# open-lab-VUSB-D.net
KiCad netlist of a schematic drawn in EAGLE
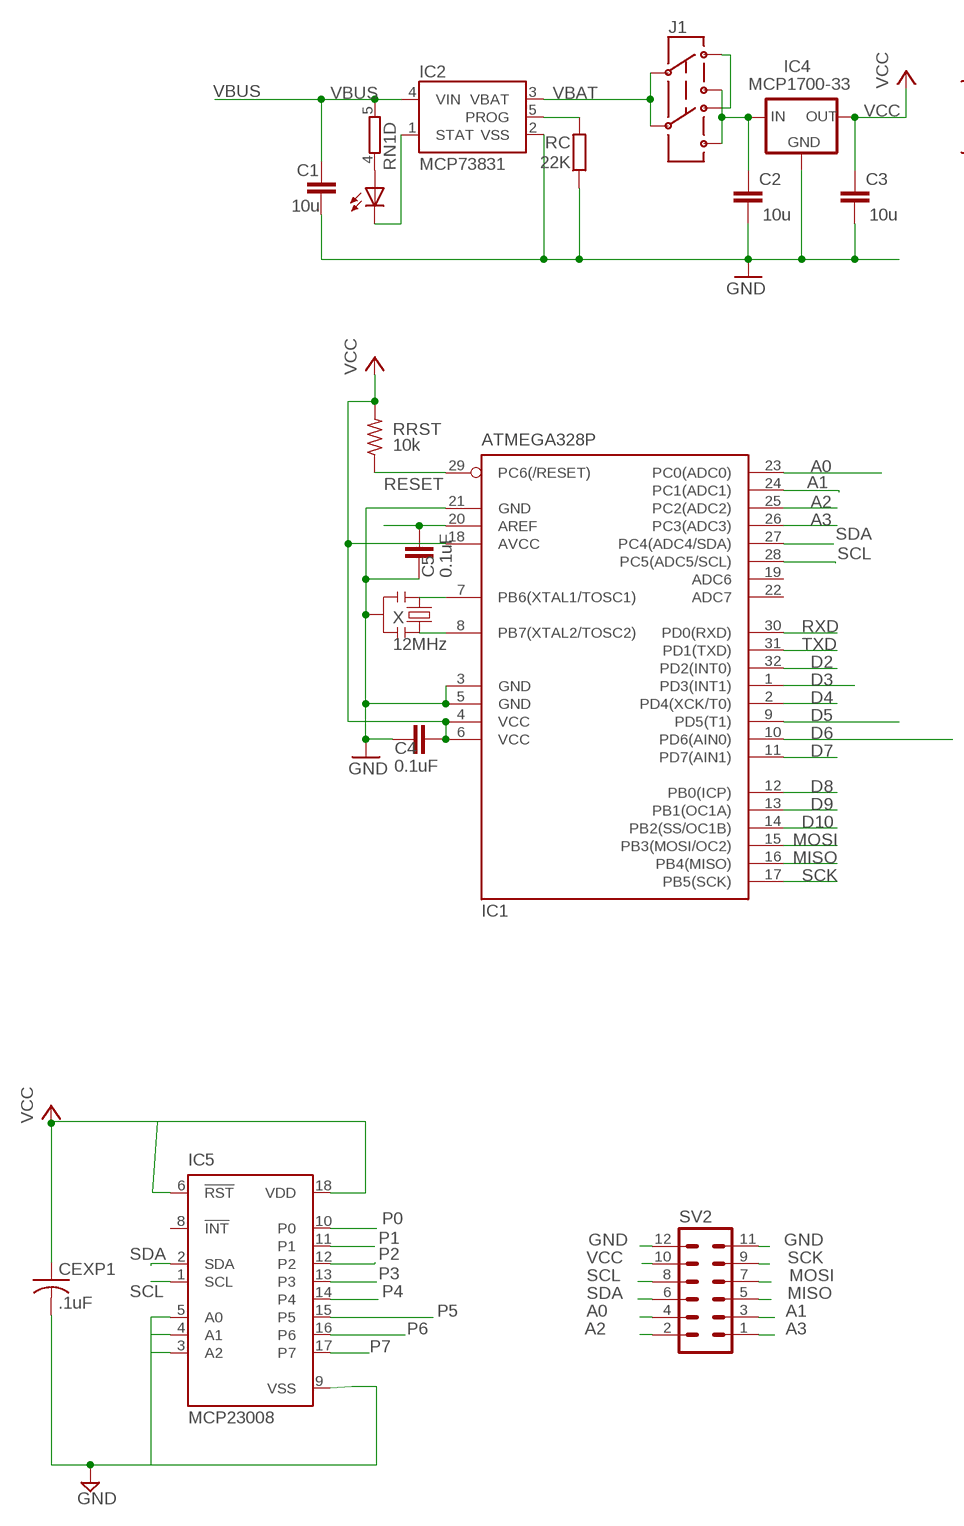
[diagram p0: schematic, sheet 1, part 1 of 2]
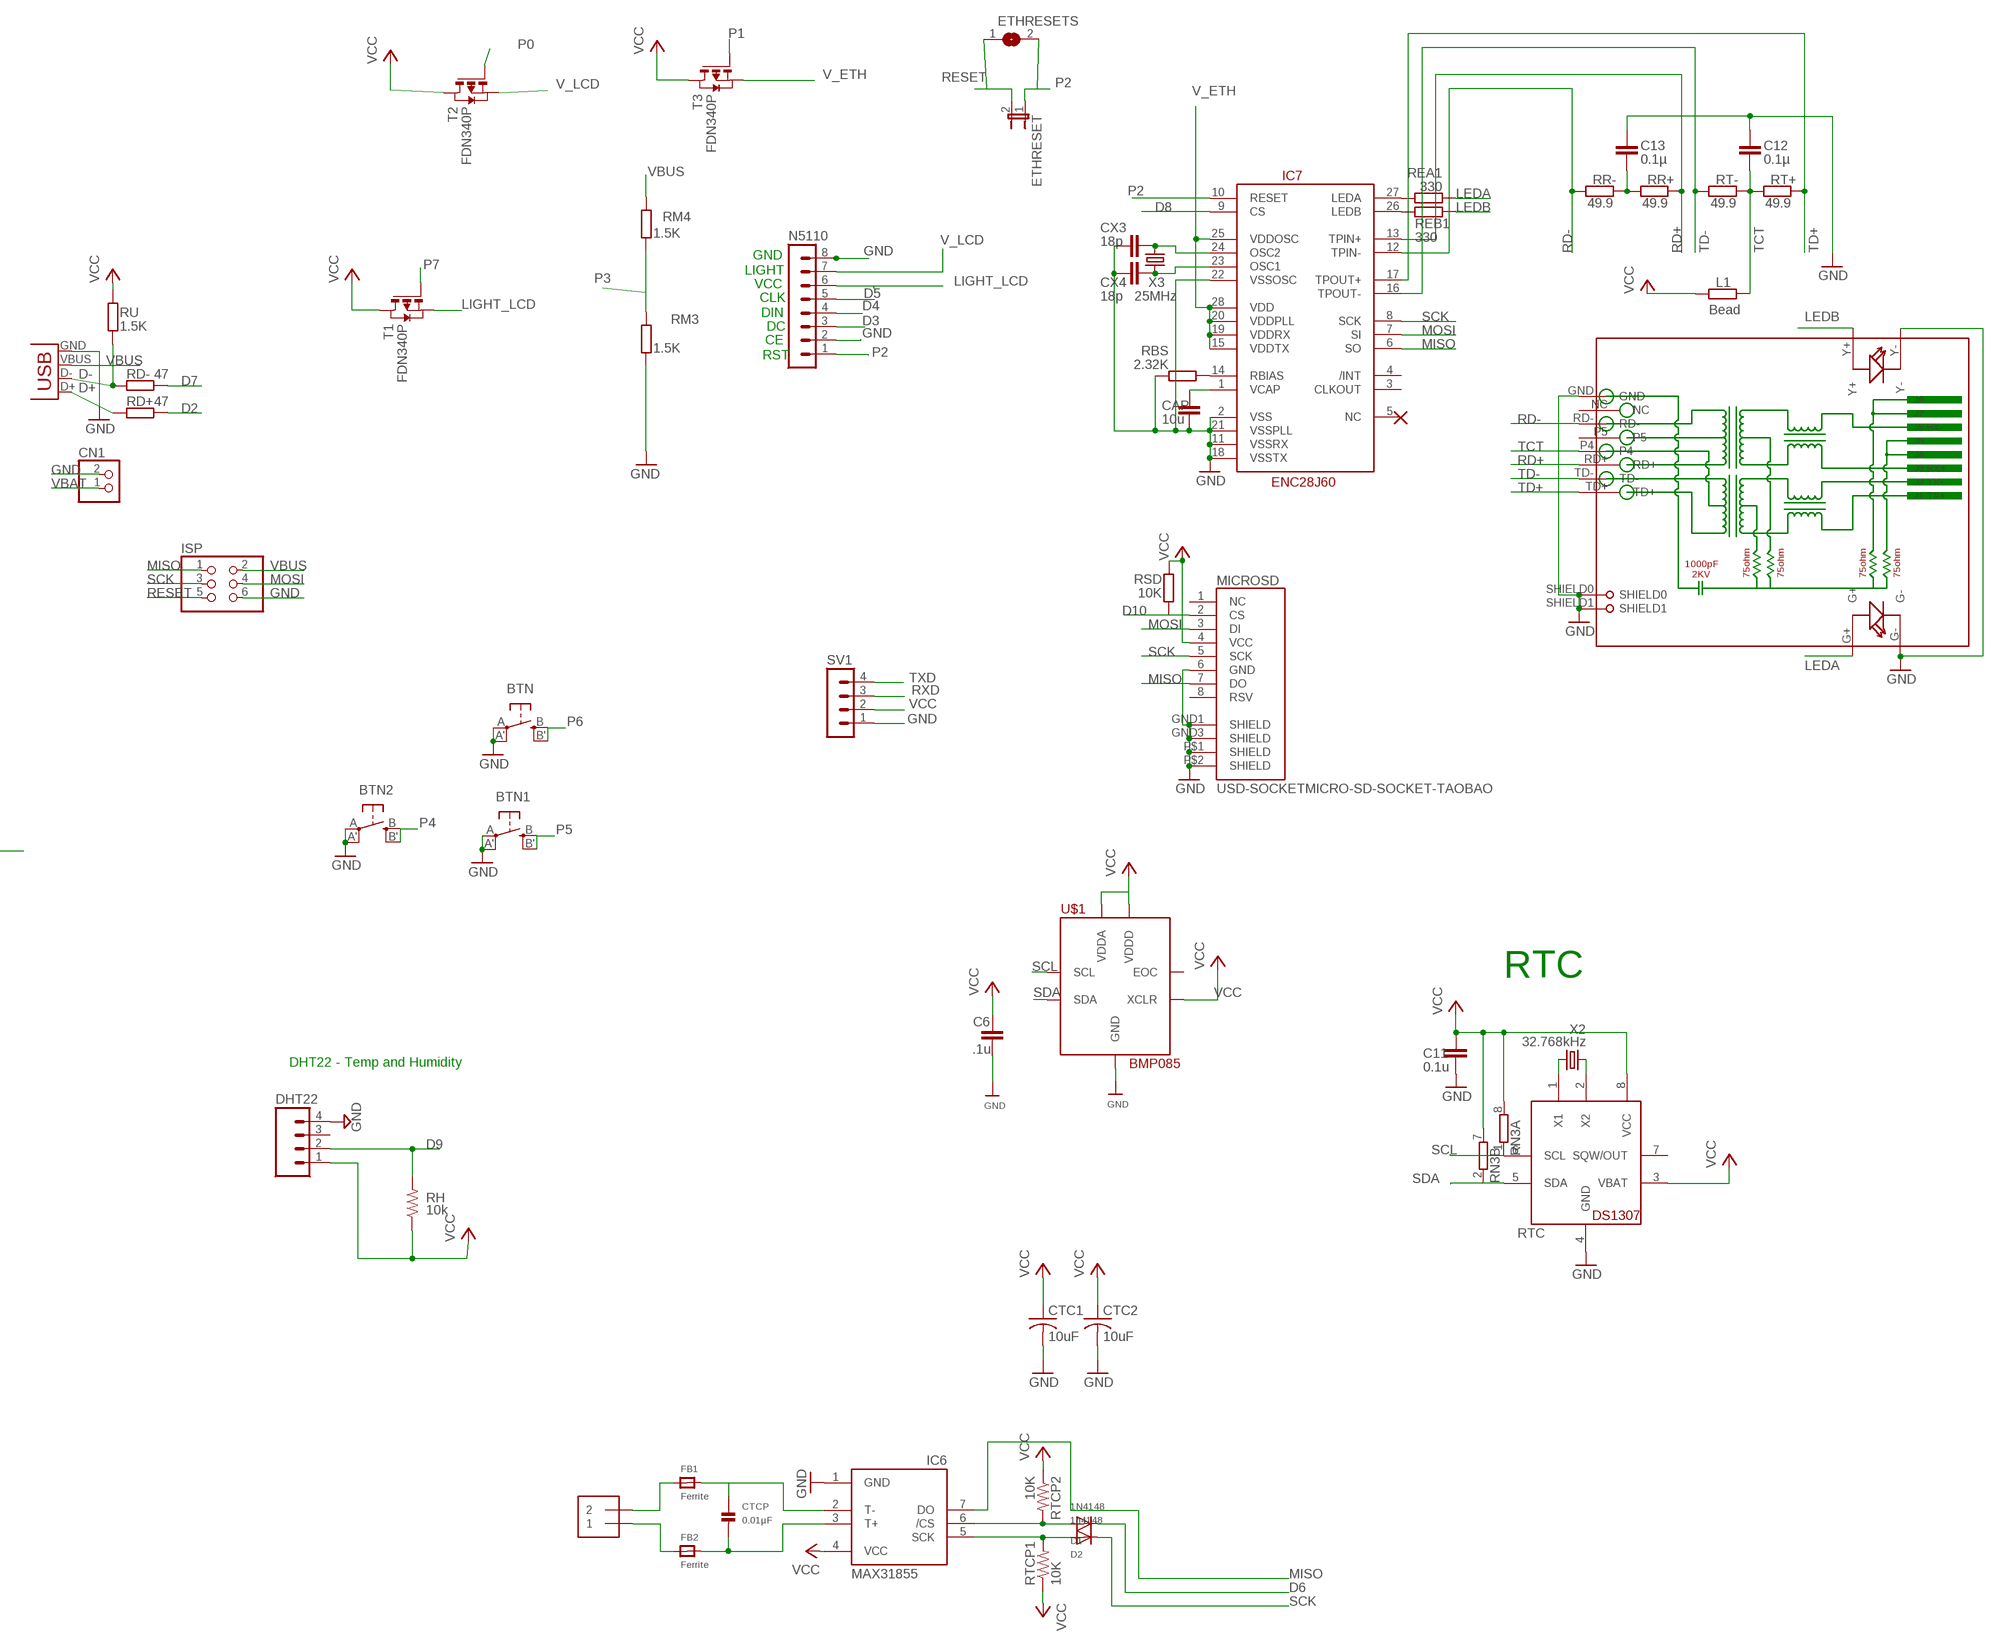
[diagram p1: schematic, sheet 1, part 2 of 2]

(export (version "E")
  (design (tool "Eeschema 10.0.6"))
  (components
    (comp (ref "BTN")
      (value "EVQQ2")
      (footprint "eagle-import:EVQ-Q2")
      (libsource (lib "eagle-import") (part "EVQQ2"))
    )
    (comp (ref "BTN1")
      (value "EVQQ2")
      (footprint "eagle-import:EVQ-Q2")
      (libsource (lib "eagle-import") (part "EVQQ2"))
    )
    (comp (ref "BTN2")
      (value "EVQQ2")
      (footprint "eagle-import:EVQ-Q2")
      (libsource (lib "eagle-import") (part "EVQQ2"))
    )
    (comp (ref "C1")
      (value "10u")
      (footprint "eagle-import:C0805")
      (libsource (lib "eagle-import") (part "resistor_C-EUC0805"))
    )
    (comp (ref "C2")
      (value "10u")
      (footprint "eagle-import:C0805")
      (libsource (lib "eagle-import") (part "resistor_C-EUC0805"))
    )
    (comp (ref "C3")
      (value "10u")
      (footprint "eagle-import:C0805")
      (libsource (lib "eagle-import") (part "resistor_C-EUC0805"))
    )
    (comp (ref "C4")
      (value "0.1uF")
      (footprint "eagle-import:C0805")
      (libsource (lib "eagle-import") (part "C-EUC0805"))
    )
    (comp (ref "C5")
      (value "0.1uF")
      (footprint "eagle-import:C0805")
      (libsource (lib "eagle-import") (part "C-EUC0805"))
    )
    (comp (ref "C6")
      (value ".1u")
      (footprint "eagle-import:C0805")
      (libsource (lib "eagle-import") (part "resistor_C-EUC0805"))
    )
    (comp (ref "C11")
      (value "0.1u")
      (footprint "eagle-import:C0805")
      (libsource (lib "eagle-import") (part "C-EUC0805"))
    )
    (comp (ref "C12")
      (value "0.1µ")
      (footprint "eagle-import:C0805")
      (libsource (lib "eagle-import") (part "resistor_C-EUC0805"))
    )
    (comp (ref "C13")
      (value "0.1µ")
      (footprint "eagle-import:C0805")
      (libsource (lib "eagle-import") (part "resistor_C-EUC0805"))
    )
    (comp (ref "CAP")
      (value "10u")
      (footprint "eagle-import:C0805")
      (libsource (lib "eagle-import") (part "resistor_C-EUC0805"))
    )
    (comp (ref "CEXP1")
      (value ".1uF")
      (footprint "eagle-import:C0805K")
      (libsource (lib "eagle-import") (part "C-USC0805K"))
    )
    (comp (ref "CHG")
      (value "0805")
      (footprint "eagle-import:CHIPLED_0805")
      (libsource (lib "eagle-import") (part "LEDCHIPLED_0805"))
    )
    (comp (ref "CN1")
      (value "JST_2PIN-SMT-RA")
      (footprint "eagle-import:JST-PH-2-SMT-RA")
      (libsource (lib "eagle-import") (part "JST_2PIN-SMT-RA"))
    )
    (comp (ref "CTC1")
      (value "10uF")
      (footprint "eagle-import:C0805K")
      (libsource (lib "eagle-import") (part "C-USC0805K"))
    )
    (comp (ref "CTC2")
      (value "10uF")
      (footprint "eagle-import:C0805K")
      (libsource (lib "eagle-import") (part "C-USC0805K"))
    )
    (comp (ref "CTCP")
      (value "0.01µF")
      (footprint "eagle-import:_0805")
      (libsource (lib "eagle-import") (part "CAP_CERAMIC_0805"))
    )
    (comp (ref "CX3")
      (value "18p")
      (footprint "eagle-import:C0805")
      (libsource (lib "eagle-import") (part "resistor_C-EUC0805"))
    )
    (comp (ref "CX4")
      (value "18p")
      (footprint "eagle-import:C0805")
      (libsource (lib "eagle-import") (part "resistor_C-EUC0805"))
    )
    (comp (ref "D1")
      (value "1N4148")
      (footprint "eagle-import:SOD-323F")
      (libsource (lib "eagle-import") (part "DIODESOD-323F"))
    )
    (comp (ref "D2")
      (value "1n4148")
      (footprint "eagle-import:SOD-323F")
      (libsource (lib "eagle-import") (part "DIODESOD-323F"))
    )
    (comp (ref "DHT22")
      (value "M04LOCK")
      (footprint "eagle-import:1X04_LOCK")
      (libsource (lib "eagle-import") (part "M04LOCK"))
    )
    (comp (ref "ETHRESET")
      (value "JP1E")
      (footprint "eagle-import:JP1")
      (libsource (lib "eagle-import") (part "JP1E"))
    )
    (comp (ref "ETHRESETS")
      (value "SJ")
      (footprint "eagle-import:SJ")
      (libsource (lib "eagle-import") (part "SJ"))
    )
    (comp (ref "FB1")
      (value "Ferrite")
      (footprint "eagle-import:_0805")
      (libsource (lib "eagle-import") (part "FERRITE_0805"))
    )
    (comp (ref "FB2")
      (value "Ferrite")
      (footprint "eagle-import:_0805")
      (libsource (lib "eagle-import") (part "FERRITE_0805"))
    )
    (comp (ref "IC1")
      (value "ATMEGA328P")
      (footprint "eagle-import:TQFP32-08")
      (fields (field (name "MPN") "ATMEGA8-16AU"))
      (libsource (lib "eagle-import") (part "MEGA8-AI"))
    )
    (comp (ref "IC2")
      (value "MCP73831")
      (footprint "eagle-import:SOT23-5")
      (libsource (lib "eagle-import") (part "MCP73831"))
    )
    (comp (ref "IC4")
      (value "MCP1700-33")
      (footprint "eagle-import:SOT23")
      (libsource (lib "eagle-import") (part "MCP1700SOT233"))
    )
    (comp (ref "IC5")
      (value "MCP23008")
      (footprint "eagle-import:SO18W")
      (libsource (lib "eagle-import") (part "MCP23008T"))
    )
    (comp (ref "IC6")
      (value "MAX31855")
      (footprint "eagle-import:SO08")
      (libsource (lib "eagle-import") (part "MAX6675"))
    )
    (comp (ref "IC7")
      (value "ENC28J60")
      (footprint "eagle-import:SOIC28WLONG")
      (libsource (lib "eagle-import") (part "ENC28J60SO28LONG"))
    )
    (comp (ref "ISP")
      (value "PINHD-2X3")
      (footprint "eagle-import:2X03")
      (libsource (lib "eagle-import") (part "PINHD-2X3"))
    )
    (comp (ref "J1")
      (value "AYZ0202")
      (footprint "eagle-import:AYZ0202")
      (libsource (lib "eagle-import") (part "AYZ0202"))
    )
    (comp (ref "L1")
      (value "Bead")
      (footprint "eagle-import:R0805")
      (libsource (lib "eagle-import") (part "R-EU_R0805"))
    )
    (comp (ref "MICROSD")
      (value "USD-SOCKETMICRO-SD-SOCKET-TAOBAO")
      (footprint "eagle-import:MICRO-SD-SOCKET-TAOBAO")
      (libsource (lib "eagle-import") (part "USD-SOCKETMICRO-SD-SOCKET-TAOBAO"))
    )
    (comp (ref "N5110")
      (value "MA08-1")
      (footprint "eagle-import:MA08-1")
      (libsource (lib "eagle-import") (part "MA08-1"))
    )
    (comp (ref "RBS")
      (value "2.32K")
      (footprint "eagle-import:R0805")
      (libsource (lib "eagle-import") (part "R-EU_R0805"))
    )
    (comp (ref "RC")
      (value "22K")
      (footprint "eagle-import:R0805")
      (libsource (lib "eagle-import") (part "R-EU_R0805"))
    )
    (comp (ref "RD+")
      (value "47")
      (footprint "eagle-import:R0805")
      (libsource (lib "eagle-import") (part "R-EU_R0805"))
    )
    (comp (ref "RD-")
      (value "47")
      (footprint "eagle-import:R0805")
      (libsource (lib "eagle-import") (part "R-EU_R0805"))
    )
    (comp (ref "REA1")
      (value "330")
      (footprint "eagle-import:R0805")
      (libsource (lib "eagle-import") (part "R-EU_R0805"))
    )
    (comp (ref "REB1")
      (value "330")
      (footprint "eagle-import:R0805")
      (libsource (lib "eagle-import") (part "R-EU_R0805"))
    )
    (comp (ref "RH")
      (value "10k")
      (footprint "eagle-import:R0805@1")
      (libsource (lib "eagle-import") (part "rcl_R-US_R0805"))
    )
    (comp (ref "RJ45")
      (value "HR911105A")
      (footprint "eagle-import:HR911105A")
      (libsource (lib "eagle-import") (part "HR911105A"))
    )
    (comp (ref "RM3")
      (value "1.5K")
      (footprint "eagle-import:R0805")
      (libsource (lib "eagle-import") (part "R-EU_R0805"))
    )
    (comp (ref "RM4")
      (value "1.5K")
      (footprint "eagle-import:R0805")
      (libsource (lib "eagle-import") (part "R-EU_R0805"))
    )
    (comp (ref "RN1")
      (value "4R-NEXB38V")
      (footprint "eagle-import:EXB38V")
      (libsource (lib "eagle-import") (part "4R-NEXB38V"))
    )
    (comp (ref "RN3")
      (value "4R-NEXB38V")
      (footprint "eagle-import:EXB38V")
      (libsource (lib "eagle-import") (part "4R-NEXB38V"))
    )
    (comp (ref "RR+")
      (value "49.9")
      (footprint "eagle-import:R0805")
      (libsource (lib "eagle-import") (part "R-EU_R0805"))
    )
    (comp (ref "RR-")
      (value "49.9")
      (footprint "eagle-import:R0805")
      (libsource (lib "eagle-import") (part "R-EU_R0805"))
    )
    (comp (ref "RRST")
      (value "10k")
      (footprint "eagle-import:R0805@1")
      (libsource (lib "eagle-import") (part "rcl_R-US_R0805"))
    )
    (comp (ref "RSD")
      (value "10K")
      (footprint "eagle-import:R0805")
      (libsource (lib "eagle-import") (part "R-EU_R0805"))
    )
    (comp (ref "RT+")
      (value "49.9")
      (footprint "eagle-import:R0805")
      (libsource (lib "eagle-import") (part "R-EU_R0805"))
    )
    (comp (ref "RT-")
      (value "49.9")
      (footprint "eagle-import:R0805")
      (libsource (lib "eagle-import") (part "R-EU_R0805"))
    )
    (comp (ref "RTC")
      (value "DS1307")
      (footprint "eagle-import:SO08")
      (libsource (lib "eagle-import") (part "DS1307SOIC"))
    )
    (comp (ref "RTCP1")
      (value "10K")
      (footprint "eagle-import:R0805")
      (libsource (lib "eagle-import") (part "R-US_R0805"))
    )
    (comp (ref "RTCP2")
      (value "10K")
      (footprint "eagle-import:R0805")
      (libsource (lib "eagle-import") (part "R-US_R0805"))
    )
    (comp (ref "RU")
      (value "1.5K")
      (footprint "eagle-import:R0805")
      (libsource (lib "eagle-import") (part "R-EU_R0805"))
    )
    (comp (ref "SV1")
      (value "MA04-1")
      (footprint "eagle-import:MA04-1")
      (libsource (lib "eagle-import") (part "MA04-1"))
    )
    (comp (ref "SV2")
      (value "MA06-2")
      (footprint "eagle-import:MA06-2")
      (libsource (lib "eagle-import") (part "MA06-2"))
    )
    (comp (ref "T1")
      (value "FDN340P")
      (footprint "eagle-import:SOT-23")
      (libsource (lib "eagle-import") (part "PMOSSOT23"))
    )
    (comp (ref "T2")
      (value "FDN340P")
      (footprint "eagle-import:SOT-23")
      (libsource (lib "eagle-import") (part "PMOSSOT23"))
    )
    (comp (ref "T3")
      (value "FDN340P")
      (footprint "eagle-import:SOT-23")
      (libsource (lib "eagle-import") (part "PMOSSOT23"))
    )
    (comp (ref "TCPL")
      (value "1X2-3.5MM")
      (footprint "eagle-import:1X2-3.5MM")
      (libsource (lib "eagle-import") (part "1X2-3.5MM"))
    )
    (comp (ref "U$1")
      (value "BMP085")
      (footprint "eagle-import:BMP085")
      (libsource (lib "eagle-import") (part "BMP085"))
    )
    (comp (ref "X")
      (value "12MHz")
      (footprint "eagle-import:RESONATOR-SMD")
      (libsource (lib "eagle-import") (part "RESONATORSMD"))
    )
    (comp (ref "X1")
      (value "USBSMD")
      (footprint "eagle-import:USB-MINIB")
      (libsource (lib "eagle-import") (part "USBSMD"))
    )
    (comp (ref "X2")
      (value "32.768kHz")
      (footprint "eagle-import:TC26H")
      (libsource (lib "eagle-import") (part "crystal_CRYSTALTC26H"))
    )
    (comp (ref "X3")
      (value "25MHz")
      (footprint "eagle-import:HC49U-V")
      (libsource (lib "eagle-import") (part "CRYSTALHC49UV"))
    )
  )
  (nets
    (net (code "1") (name "/A0") (class "Default")
      (node (ref "IC1") (pin "23") (pinfunction "PC0(ADC0)_23") (pintype "bidirectional"))
      (node (ref "SV2") (pin "4") (pinfunction "4_4") (pintype "passive"))
    )
    (net (code "2") (name "/A1") (class "Default")
      (node (ref "IC1") (pin "24") (pinfunction "PC1(ADC1)_24") (pintype "bidirectional"))
      (node (ref "SV2") (pin "3") (pinfunction "3_3") (pintype "passive"))
    )
    (net (code "3") (name "/A2") (class "Default")
      (node (ref "IC1") (pin "25") (pinfunction "PC2(ADC2)_25") (pintype "bidirectional"))
      (node (ref "SV2") (pin "2") (pinfunction "2_2") (pintype "passive"))
    )
    (net (code "4") (name "/A3") (class "Default")
      (node (ref "IC1") (pin "26") (pinfunction "PC3(ADC3)_26") (pintype "bidirectional"))
      (node (ref "SV2") (pin "1") (pinfunction "1_1") (pintype "passive"))
    )
    (net (code "5") (name "/D+") (class "Default")
      (node (ref "RD+") (pin "1") (pinfunction "1_1") (pintype "passive"))
      (node (ref "X1") (pin "D+") (pinfunction "D+_D+") (pintype "bidirectional"))
    )
    (net (code "6") (name "/D-") (class "Default")
      (node (ref "RD-") (pin "1") (pinfunction "1_1") (pintype "passive"))
      (node (ref "RU") (pin "1") (pinfunction "1_1") (pintype "passive"))
      (node (ref "X1") (pin "D-") (pinfunction "D-_D-") (pintype "bidirectional"))
    )
    (net (code "7") (name "/D2") (class "Default")
      (node (ref "IC1") (pin "32") (pinfunction "PD2(INT0)_32") (pintype "bidirectional"))
      (node (ref "RD+") (pin "2") (pinfunction "2_2") (pintype "passive"))
    )
    (net (code "8") (name "/D3") (class "Default")
      (node (ref "IC1") (pin "1") (pinfunction "PD3(INT1)_1") (pintype "bidirectional"))
      (node (ref "N5110") (pin "3") (pinfunction "3_3") (pintype "passive"))
    )
    (net (code "9") (name "/D4") (class "Default")
      (node (ref "IC1") (pin "2") (pinfunction "PD4(XCK/T0)_2") (pintype "bidirectional"))
      (node (ref "N5110") (pin "4") (pinfunction "4_4") (pintype "passive"))
    )
    (net (code "10") (name "/D5") (class "Default")
      (node (ref "IC1") (pin "9") (pinfunction "PD5(T1)_9") (pintype "bidirectional"))
      (node (ref "N5110") (pin "5") (pinfunction "5_5") (pintype "passive"))
    )
    (net (code "11") (name "/D6") (class "Default")
      (node (ref "D1") (pin "C") (pinfunction "C_C") (pintype "passive"))
      (node (ref "IC1") (pin "10") (pinfunction "PD6(AIN0)_10") (pintype "bidirectional"))
    )
    (net (code "12") (name "/D7") (class "Default")
      (node (ref "IC1") (pin "11") (pinfunction "PD7(AIN1)_11") (pintype "bidirectional"))
      (node (ref "RD-") (pin "2") (pinfunction "2_2") (pintype "passive"))
    )
    (net (code "13") (name "/D8") (class "Default")
      (node (ref "IC1") (pin "12") (pinfunction "PB0(ICP)_12") (pintype "bidirectional"))
      (node (ref "IC7") (pin "9") (pinfunction "CS_9") (pintype "bidirectional"))
    )
    (net (code "14") (name "/D9") (class "Default")
      (node (ref "DHT22") (pin "2") (pinfunction "2_2") (pintype "passive"))
      (node (ref "IC1") (pin "13") (pinfunction "PB1(OC1A)_13") (pintype "bidirectional"))
      (node (ref "RH") (pin "2") (pinfunction "2_2") (pintype "passive"))
    )
    (net (code "15") (name "/D10") (class "Default")
      (node (ref "IC1") (pin "14") (pinfunction "PB2(SS/OC1B)_14") (pintype "bidirectional"))
      (node (ref "MICROSD") (pin "2") (pinfunction "CS_2") (pintype "bidirectional"))
      (node (ref "RSD") (pin "1") (pinfunction "1_1") (pintype "passive"))
    )
    (net (code "16") (name "/LEDA") (class "Default")
      (node (ref "REA1") (pin "2") (pinfunction "2_2") (pintype "passive"))
      (node (ref "RJ45") (pin "G+") (pinfunction "G+_G+") (pintype "bidirectional"))
    )
    (net (code "17") (name "/LEDB") (class "Default")
      (node (ref "REB1") (pin "2") (pinfunction "2_2") (pintype "passive"))
      (node (ref "RJ45") (pin "Y+") (pinfunction "Y+_Y+") (pintype "bidirectional"))
    )
    (net (code "18") (name "/LIGHT_LCD") (class "Default")
      (node (ref "N5110") (pin "6") (pinfunction "6_6") (pintype "passive"))
      (node (ref "T1") (pin "2") (pinfunction "S_2") (pintype "passive"))
    )
    (net (code "19") (name "/MISO") (class "Default")
      (node (ref "IC1") (pin "16") (pinfunction "PB4(MISO)_16") (pintype "bidirectional"))
      (node (ref "IC6") (pin "7") (pinfunction "DO_7") (pintype "output"))
      (node (ref "IC7") (pin "6") (pinfunction "SO_6") (pintype "bidirectional"))
      (node (ref "ISP") (pin "1") (pinfunction "1_1") (pintype "passive"))
      (node (ref "MICROSD") (pin "7") (pinfunction "DO_7") (pintype "bidirectional"))
      (node (ref "SV2") (pin "5") (pinfunction "5_5") (pintype "passive"))
    )
    (net (code "20") (name "/MOSI") (class "Default")
      (node (ref "IC1") (pin "15") (pinfunction "PB3(MOSI/OC2)_15") (pintype "bidirectional"))
      (node (ref "IC7") (pin "7") (pinfunction "SI_7") (pintype "bidirectional"))
      (node (ref "ISP") (pin "4") (pinfunction "4_4") (pintype "passive"))
      (node (ref "MICROSD") (pin "3") (pinfunction "DI_3") (pintype "bidirectional"))
      (node (ref "SV2") (pin "7") (pinfunction "7_7") (pintype "passive"))
    )
    (net (code "21") (name "/P0") (class "Default")
      (node (ref "IC5") (pin "10") (pinfunction "P0_10") (pintype "bidirectional"))
      (node (ref "T2") (pin "3") (pinfunction "G_3") (pintype "passive"))
    )
    (net (code "22") (name "/P1") (class "Default")
      (node (ref "IC5") (pin "11") (pinfunction "P1_11") (pintype "bidirectional"))
      (node (ref "T3") (pin "3") (pinfunction "G_3") (pintype "passive"))
    )
    (net (code "23") (name "/P2") (class "Default")
      (node (ref "ETHRESET") (pin "1") (pinfunction "1_1") (pintype "passive"))
      (node (ref "ETHRESETS") (pin "2") (pinfunction "2_2") (pintype "passive"))
      (node (ref "IC5") (pin "12") (pinfunction "P2_12") (pintype "bidirectional"))
      (node (ref "IC7") (pin "10") (pinfunction "RESET_10") (pintype "bidirectional"))
      (node (ref "N5110") (pin "1") (pinfunction "1_1") (pintype "passive"))
    )
    (net (code "24") (name "/P3") (class "Default")
      (node (ref "IC5") (pin "13") (pinfunction "P3_13") (pintype "bidirectional"))
      (node (ref "RM3") (pin "2") (pinfunction "2_2") (pintype "passive"))
      (node (ref "RM4") (pin "1") (pinfunction "1_1") (pintype "passive"))
    )
    (net (code "25") (name "/P4") (class "Default")
      (node (ref "BTN2") (pin "B") (pinfunction "S_B") (pintype "passive"))
      (node (ref "BTN2") (pin "B'") (pinfunction "S1_B'") (pintype "passive"))
      (node (ref "IC5") (pin "14") (pinfunction "P4_14") (pintype "bidirectional"))
    )
    (net (code "26") (name "/P5") (class "Default")
      (node (ref "BTN1") (pin "B") (pinfunction "S_B") (pintype "passive"))
      (node (ref "BTN1") (pin "B'") (pinfunction "S1_B'") (pintype "passive"))
      (node (ref "IC5") (pin "15") (pinfunction "P5_15") (pintype "bidirectional"))
    )
    (net (code "27") (name "/P6") (class "Default")
      (node (ref "BTN") (pin "B") (pinfunction "S_B") (pintype "passive"))
      (node (ref "BTN") (pin "B'") (pinfunction "S1_B'") (pintype "passive"))
      (node (ref "IC5") (pin "16") (pinfunction "P6_16") (pintype "bidirectional"))
    )
    (net (code "28") (name "/P7") (class "Default")
      (node (ref "IC5") (pin "17") (pinfunction "P7_17") (pintype "bidirectional"))
      (node (ref "T1") (pin "3") (pinfunction "G_3") (pintype "passive"))
    )
    (net (code "29") (name "/RD+") (class "Default")
      (node (ref "IC7") (pin "13") (pinfunction "TPIN+_13") (pintype "bidirectional"))
      (node (ref "RJ45") (pin "RD+") (pinfunction "RD+_RD+") (pintype "bidirectional"))
      (node (ref "RR+") (pin "1") (pinfunction "1_1") (pintype "passive"))
    )
    (net (code "30") (name "/RD-") (class "Default")
      (node (ref "IC7") (pin "12") (pinfunction "TPIN-_12") (pintype "bidirectional"))
      (node (ref "RJ45") (pin "RD-") (pinfunction "RD-_RD-") (pintype "bidirectional"))
      (node (ref "RR-") (pin "2") (pinfunction "2_2") (pintype "passive"))
    )
    (net (code "31") (name "/RESET") (class "Default")
      (node (ref "ETHRESET") (pin "2") (pinfunction "2_2") (pintype "passive"))
      (node (ref "ETHRESETS") (pin "1") (pinfunction "1_1") (pintype "passive"))
      (node (ref "IC1") (pin "29") (pinfunction "PC6(/RESET)_29") (pintype "bidirectional"))
      (node (ref "ISP") (pin "5") (pinfunction "5_5") (pintype "passive"))
      (node (ref "RRST") (pin "1") (pinfunction "1_1") (pintype "passive"))
    )
    (net (code "32") (name "/RXD") (class "Default")
      (node (ref "IC1") (pin "30") (pinfunction "PD0(RXD)_30") (pintype "bidirectional"))
      (node (ref "SV1") (pin "3") (pinfunction "3_3") (pintype "passive"))
    )
    (net (code "33") (name "/SCK") (class "Default")
      (node (ref "D2") (pin "C") (pinfunction "C_C") (pintype "passive"))
      (node (ref "IC1") (pin "17") (pinfunction "PB5(SCK)_17") (pintype "bidirectional"))
      (node (ref "IC7") (pin "8") (pinfunction "SCK_8") (pintype "bidirectional"))
      (node (ref "ISP") (pin "3") (pinfunction "3_3") (pintype "passive"))
      (node (ref "MICROSD") (pin "5") (pinfunction "SCK_5") (pintype "bidirectional"))
      (node (ref "SV2") (pin "9") (pinfunction "9_9") (pintype "passive"))
    )
    (net (code "34") (name "/SCL") (class "Default")
      (node (ref "IC1") (pin "28") (pinfunction "PC5(ADC5/SCL)_28") (pintype "bidirectional"))
      (node (ref "IC5") (pin "1") (pinfunction "SCL_1") (pintype "input"))
      (node (ref "RN3") (pin "1") (pinfunction "1_1") (pintype "passive"))
      (node (ref "RTC") (pin "6") (pinfunction "SCL_6") (pintype "bidirectional"))
      (node (ref "SV2") (pin "8") (pinfunction "8_8") (pintype "passive"))
      (node (ref "U$1") (pin "P$6") (pinfunction "SCL_P$6") (pintype "bidirectional"))
    )
    (net (code "35") (name "/SDA") (class "Default")
      (node (ref "IC1") (pin "27") (pinfunction "PC4(ADC4/SDA)_27") (pintype "bidirectional"))
      (node (ref "IC5") (pin "2") (pinfunction "SDA_2") (pintype "bidirectional"))
      (node (ref "RN3") (pin "2") (pinfunction "1_2") (pintype "passive"))
      (node (ref "RTC") (pin "5") (pinfunction "SDA_5") (pintype "bidirectional"))
      (node (ref "SV2") (pin "6") (pinfunction "6_6") (pintype "passive"))
      (node (ref "U$1") (pin "P$7") (pinfunction "SDA_P$7") (pintype "bidirectional"))
    )
    (net (code "36") (name "/TCT") (class "Default")
      (node (ref "C12") (pin "2") (pinfunction "2_2") (pintype "passive"))
      (node (ref "L1") (pin "1") (pinfunction "1_1") (pintype "passive"))
      (node (ref "RJ45") (pin "P4") (pinfunction "P4_P4") (pintype "bidirectional"))
      (node (ref "RT+") (pin "2") (pinfunction "2_2") (pintype "passive"))
      (node (ref "RT-") (pin "1") (pinfunction "1_1") (pintype "passive"))
    )
    (net (code "37") (name "/TD+") (class "Default")
      (node (ref "IC7") (pin "17") (pinfunction "TPOUT+_17") (pintype "bidirectional"))
      (node (ref "RJ45") (pin "TD+") (pinfunction "TD+_TD+") (pintype "bidirectional"))
      (node (ref "RT+") (pin "1") (pinfunction "1_1") (pintype "passive"))
    )
    (net (code "38") (name "/TD-") (class "Default")
      (node (ref "IC7") (pin "16") (pinfunction "TPOUT-_16") (pintype "bidirectional"))
      (node (ref "RJ45") (pin "TD-") (pinfunction "TD-_TD-") (pintype "bidirectional"))
      (node (ref "RT-") (pin "2") (pinfunction "2_2") (pintype "passive"))
    )
    (net (code "39") (name "/TXD") (class "Default")
      (node (ref "IC1") (pin "31") (pinfunction "PD1(TXD)_31") (pintype "bidirectional"))
      (node (ref "SV1") (pin "4") (pinfunction "4_4") (pintype "passive"))
    )
    (net (code "40") (name "/VBAT") (class "Default")
      (node (ref "CN1") (pin "1") (pinfunction "2_1") (pintype "passive"))
      (node (ref "IC2") (pin "3") (pinfunction "VBAT_3") (pintype "power_in"))
      (node (ref "J1") (pin "2") (pinfunction "2_2") (pintype "bidirectional"))
      (node (ref "J1") (pin "5") (pinfunction "5_5") (pintype "bidirectional"))
    )
    (net (code "41") (name "/VBUS") (class "Default")
      (node (ref "C1") (pin "1") (pinfunction "1_1") (pintype "passive"))
      (node (ref "IC2") (pin "4") (pinfunction "VIN_4") (pintype "power_in"))
      (node (ref "ISP") (pin "2") (pinfunction "2_2") (pintype "passive"))
      (node (ref "RM4") (pin "2") (pinfunction "2_2") (pintype "passive"))
      (node (ref "RN1") (pin "5") (pinfunction "2_5") (pintype "passive"))
      (node (ref "X1") (pin "VBUS") (pinfunction "VBUS_VBUS") (pintype "bidirectional"))
    )
    (net (code "42") (name "/V_ETH") (class "Default")
      (node (ref "IC7") (pin "15") (pinfunction "VDDTX_15") (pintype "bidirectional"))
      (node (ref "IC7") (pin "19") (pinfunction "VDDRX_19") (pintype "bidirectional"))
      (node (ref "IC7") (pin "20") (pinfunction "VDDPLL_20") (pintype "bidirectional"))
      (node (ref "IC7") (pin "25") (pinfunction "VDDOSC_25") (pintype "bidirectional"))
      (node (ref "IC7") (pin "28") (pinfunction "VDD_28") (pintype "bidirectional"))
      (node (ref "T3") (pin "2") (pinfunction "S_2") (pintype "passive"))
    )
    (net (code "43") (name "/V_LCD") (class "Default")
      (node (ref "N5110") (pin "7") (pinfunction "7_7") (pintype "passive"))
      (node (ref "T2") (pin "2") (pinfunction "S_2") (pintype "passive"))
    )
    (net (code "44") (name "GND") (class "Default")
      (node (ref "BTN") (pin "A") (pinfunction "P_A") (pintype "passive"))
      (node (ref "BTN") (pin "A'") (pinfunction "P1_A'") (pintype "passive"))
      (node (ref "BTN1") (pin "A") (pinfunction "P_A") (pintype "passive"))
      (node (ref "BTN1") (pin "A'") (pinfunction "P1_A'") (pintype "passive"))
      (node (ref "BTN2") (pin "A") (pinfunction "P_A") (pintype "passive"))
      (node (ref "BTN2") (pin "A'") (pinfunction "P1_A'") (pintype "passive"))
      (node (ref "C1") (pin "2") (pinfunction "2_2") (pintype "passive"))
      (node (ref "C11") (pin "2") (pinfunction "2_2") (pintype "passive"))
      (node (ref "C12") (pin "1") (pinfunction "1_1") (pintype "passive"))
      (node (ref "C13") (pin "1") (pinfunction "1_1") (pintype "passive"))
      (node (ref "C2") (pin "2") (pinfunction "2_2") (pintype "passive"))
      (node (ref "C3") (pin "2") (pinfunction "2_2") (pintype "passive"))
      (node (ref "C4") (pin "1") (pinfunction "1_1") (pintype "passive"))
      (node (ref "C5") (pin "1") (pinfunction "1_1") (pintype "passive"))
      (node (ref "C6") (pin "2") (pinfunction "2_2") (pintype "passive"))
      (node (ref "CAP") (pin "2") (pinfunction "2_2") (pintype "passive"))
      (node (ref "CEXP1") (pin "2") (pinfunction "2_2") (pintype "passive"))
      (node (ref "CN1") (pin "2") (pinfunction "1_2") (pintype "passive"))
      (node (ref "CTC1") (pin "2") (pinfunction "2_2") (pintype "passive"))
      (node (ref "CTC2") (pin "2") (pinfunction "2_2") (pintype "passive"))
      (node (ref "CX3") (pin "2") (pinfunction "2_2") (pintype "passive"))
      (node (ref "CX4") (pin "2") (pinfunction "2_2") (pintype "passive"))
      (node (ref "DHT22") (pin "4") (pinfunction "4_4") (pintype "passive"))
      (node (ref "IC1") (pin "21") (pinfunction "GND_21") (pintype "power_in"))
      (node (ref "IC1") (pin "3") (pinfunction "GND_3") (pintype "power_in"))
      (node (ref "IC1") (pin "5") (pinfunction "GND_5") (pintype "power_in"))
      (node (ref "IC2") (pin "2") (pinfunction "VSS_2") (pintype "power_in"))
      (node (ref "IC4") (pin "1") (pinfunction "GND_1") (pintype "input"))
      (node (ref "IC5") (pin "3") (pinfunction "A2_3") (pintype "input"))
      (node (ref "IC5") (pin "4") (pinfunction "A1_4") (pintype "input"))
      (node (ref "IC5") (pin "5") (pinfunction "A0_5") (pintype "input"))
      (node (ref "IC5") (pin "9") (pinfunction "VSS_9") (pintype "power_in"))
      (node (ref "IC6") (pin "1") (pinfunction "GND_1") (pintype "power_in"))
      (node (ref "IC7") (pin "11") (pinfunction "VSSRX_11") (pintype "bidirectional"))
      (node (ref "IC7") (pin "18") (pinfunction "VSSTX_18") (pintype "bidirectional"))
      (node (ref "IC7") (pin "2") (pinfunction "VSS_2") (pintype "bidirectional"))
      (node (ref "IC7") (pin "21") (pinfunction "VSSPLL_21") (pintype "bidirectional"))
      (node (ref "IC7") (pin "22") (pinfunction "VSSOSC_22") (pintype "bidirectional"))
      (node (ref "ISP") (pin "6") (pinfunction "6_6") (pintype "passive"))
      (node (ref "MICROSD") (pin "6") (pinfunction "GND_6") (pintype "bidirectional"))
      (node (ref "MICROSD") (pin "GND1") (pinfunction "SHIELD_GND1") (pintype "bidirectional"))
      (node (ref "MICROSD") (pin "GND3") (pinfunction "SHIELD_GND3") (pintype "bidirectional"))
      (node (ref "MICROSD") (pin "P$1") (pinfunction "SHIELD_P$1") (pintype "bidirectional"))
      (node (ref "MICROSD") (pin "P$2") (pinfunction "SHIELD_P$2") (pintype "bidirectional"))
      (node (ref "N5110") (pin "2") (pinfunction "2_2") (pintype "passive"))
      (node (ref "N5110") (pin "8") (pinfunction "8_8") (pintype "passive"))
      (node (ref "RBS") (pin "1") (pinfunction "1_1") (pintype "passive"))
      (node (ref "RC") (pin "1") (pinfunction "1_1") (pintype "passive"))
      (node (ref "RJ45") (pin "G-") (pinfunction "G-_G-") (pintype "bidirectional"))
      (node (ref "RJ45") (pin "GND") (pinfunction "GND_GND") (pintype "bidirectional"))
      (node (ref "RJ45") (pin "SHIELD0") (pinfunction "SHIELD0_SHIELD0") (pintype "bidirectional"))
      (node (ref "RJ45") (pin "SHIELD1") (pinfunction "SHIELD1_SHIELD1") (pintype "bidirectional"))
      (node (ref "RJ45") (pin "Y-") (pinfunction "Y-_Y-") (pintype "bidirectional"))
      (node (ref "RM3") (pin "1") (pinfunction "1_1") (pintype "passive"))
      (node (ref "RTC") (pin "4") (pinfunction "GND_4") (pintype "power_in"))
      (node (ref "SV1") (pin "1") (pinfunction "1_1") (pintype "passive"))
      (node (ref "SV2") (pin "11") (pinfunction "11_11") (pintype "passive"))
      (node (ref "SV2") (pin "12") (pinfunction "12_12") (pintype "passive"))
      (node (ref "U$1") (pin "P$1") (pinfunction "GND_P$1") (pintype "power_in"))
      (node (ref "X") (pin "2") (pinfunction "2_2") (pintype "passive"))
      (node (ref "X1") (pin "GND") (pinfunction "GND_GND") (pintype "bidirectional"))
    )
    (net (code "45") (name "Net-(C13-Pad2)") (class "Default")
      (node (ref "C13") (pin "2") (pinfunction "2_2") (pintype "passive"))
      (node (ref "RR+") (pin "2") (pinfunction "2_2") (pintype "passive"))
      (node (ref "RR-") (pin "1") (pinfunction "1_1") (pintype "passive"))
    )
    (net (code "46") (name "Net-(CTCP-P$1)") (class "Default")
      (node (ref "CTCP") (pin "1") (pinfunction "P$1_1") (pintype "passive"))
      (node (ref "FB1") (pin "2") (pinfunction "P$2_2") (pintype "passive"))
      (node (ref "IC6") (pin "2") (pinfunction "T-_2") (pintype "input"))
    )
    (net (code "47") (name "Net-(CTCP-P$2)") (class "Default")
      (node (ref "CTCP") (pin "2") (pinfunction "P$2_2") (pintype "passive"))
      (node (ref "FB2") (pin "2") (pinfunction "P$2_2") (pintype "passive"))
      (node (ref "IC6") (pin "3") (pinfunction "T+_3") (pintype "input"))
    )
    (net (code "48") (name "Net-(FB1-P$1)") (class "Default")
      (node (ref "FB1") (pin "1") (pinfunction "P$1_1") (pintype "passive"))
      (node (ref "TCPL") (pin "2") (pinfunction "2_2") (pintype "passive"))
    )
    (net (code "49") (name "Net-(FB2-P$1)") (class "Default")
      (node (ref "FB2") (pin "1") (pinfunction "P$1_1") (pintype "passive"))
      (node (ref "TCPL") (pin "1") (pinfunction "1_1") (pintype "passive"))
    )
    (net (code "50") (name "Net-(IC1-AREF)") (class "Default")
      (node (ref "C5") (pin "2") (pinfunction "2_2") (pintype "passive"))
      (node (ref "IC1") (pin "20") (pinfunction "AREF_20") (pintype "passive"))
    )
    (net (code "51") (name "Net-(IC1-PB6(XTAL1{slash}TOSC1))") (class "Default")
      (node (ref "IC1") (pin "7") (pinfunction "PB6(XTAL1/TOSC1)_7") (pintype "bidirectional"))
      (node (ref "X") (pin "1") (pinfunction "1_1") (pintype "passive"))
    )
    (net (code "52") (name "Net-(IC1-PB7(XTAL2{slash}TOSC2))") (class "Default")
      (node (ref "IC1") (pin "8") (pinfunction "PB7(XTAL2/TOSC2)_8") (pintype "bidirectional"))
      (node (ref "X") (pin "3") (pinfunction "3_3") (pintype "passive"))
    )
    (net (code "53") (name "Net-(IC2-PROG)") (class "Default")
      (node (ref "IC2") (pin "5") (pinfunction "PROG_5") (pintype "input"))
      (node (ref "RC") (pin "2") (pinfunction "2_2") (pintype "passive"))
    )
    (net (code "54") (name "Net-(IC2-STAT)") (class "Default")
      (node (ref "CHG") (pin "C") (pinfunction "C_C") (pintype "passive"))
      (node (ref "IC2") (pin "1") (pinfunction "STAT_1") (pintype "output"))
    )
    (net (code "55") (name "Net-(IC4-IN)") (class "Default")
      (node (ref "C2") (pin "1") (pinfunction "1_1") (pintype "passive"))
      (node (ref "IC4") (pin "3") (pinfunction "IN_3") (pintype "input"))
      (node (ref "J1") (pin "1") (pinfunction "3_1") (pintype "bidirectional"))
      (node (ref "J1") (pin "4") (pinfunction "6_4") (pintype "bidirectional"))
    )
    (net (code "56") (name "Net-(IC6-SCK)") (class "Default")
      (node (ref "D2") (pin "A") (pinfunction "A_A") (pintype "passive"))
      (node (ref "IC6") (pin "5") (pinfunction "SCK_5") (pintype "input"))
      (node (ref "RTCP1") (pin "2") (pinfunction "2_2") (pintype "passive"))
    )
    (net (code "57") (name "Net-(IC6-{slash}CS)") (class "Default")
      (node (ref "D1") (pin "A") (pinfunction "A_A") (pintype "passive"))
      (node (ref "IC6") (pin "6") (pinfunction "/CS_6") (pintype "input"))
      (node (ref "RTCP2") (pin "2") (pinfunction "2_2") (pintype "passive"))
    )
    (net (code "58") (name "Net-(IC7-LEDA)") (class "Default")
      (node (ref "IC7") (pin "27") (pinfunction "LEDA_27") (pintype "bidirectional"))
      (node (ref "REA1") (pin "1") (pinfunction "1_1") (pintype "passive"))
    )
    (net (code "59") (name "Net-(IC7-LEDB)") (class "Default")
      (node (ref "IC7") (pin "26") (pinfunction "LEDB_26") (pintype "bidirectional"))
      (node (ref "REB1") (pin "1") (pinfunction "1_1") (pintype "passive"))
    )
    (net (code "60") (name "Net-(IC7-OSC1)") (class "Default")
      (node (ref "CX4") (pin "1") (pinfunction "1_1") (pintype "passive"))
      (node (ref "IC7") (pin "23") (pinfunction "OSC1_23") (pintype "bidirectional"))
      (node (ref "X3") (pin "1") (pinfunction "1_1") (pintype "passive"))
    )
    (net (code "61") (name "Net-(IC7-OSC2)") (class "Default")
      (node (ref "CX3") (pin "1") (pinfunction "1_1") (pintype "passive"))
      (node (ref "IC7") (pin "24") (pinfunction "OSC2_24") (pintype "bidirectional"))
      (node (ref "X3") (pin "2") (pinfunction "2_2") (pintype "passive"))
    )
    (net (code "62") (name "Net-(IC7-RBIAS)") (class "Default")
      (node (ref "IC7") (pin "14") (pinfunction "RBIAS_14") (pintype "bidirectional"))
      (node (ref "RBS") (pin "2") (pinfunction "2_2") (pintype "passive"))
    )
    (net (code "63") (name "Net-(IC7-VCAP)") (class "Default")
      (node (ref "CAP") (pin "1") (pinfunction "1_1") (pintype "passive"))
      (node (ref "IC7") (pin "1") (pinfunction "VCAP_1") (pintype "bidirectional"))
    )
    (net (code "64") (name "Net-(J1-1)") (class "Default")
      (node (ref "J1") (pin "3") (pinfunction "1_3") (pintype "bidirectional"))
      (node (ref "J1") (pin "6") (pinfunction "4_6") (pintype "bidirectional"))
    )
    (net (code "65") (name "Net-(RN1D-1)") (class "Default")
      (node (ref "CHG") (pin "A") (pinfunction "A_A") (pintype "passive"))
      (node (ref "RN1") (pin "4") (pinfunction "1_4") (pintype "passive"))
    )
    (net (code "66") (name "Net-(RTC-X1)") (class "Default")
      (node (ref "RTC") (pin "1") (pinfunction "X1_1") (pintype "passive"))
      (node (ref "X2") (pin "2") (pinfunction "2_2") (pintype "passive"))
    )
    (net (code "67") (name "Net-(RTC-X2)") (class "Default")
      (node (ref "RTC") (pin "2") (pinfunction "X2_2") (pintype "passive"))
      (node (ref "X2") (pin "1") (pinfunction "1_1") (pintype "passive"))
    )
    (net (code "68") (name "VCC") (class "Default")
      (node (ref "C11") (pin "1") (pinfunction "1_1") (pintype "passive"))
      (node (ref "C3") (pin "1") (pinfunction "1_1") (pintype "passive"))
      (node (ref "C4") (pin "2") (pinfunction "2_2") (pintype "passive"))
      (node (ref "C6") (pin "1") (pinfunction "1_1") (pintype "passive"))
      (node (ref "CEXP1") (pin "1") (pinfunction "1_1") (pintype "passive"))
      (node (ref "CTC1") (pin "1") (pinfunction "1_1") (pintype "passive"))
      (node (ref "CTC2") (pin "1") (pinfunction "1_1") (pintype "passive"))
      (node (ref "DHT22") (pin "1") (pinfunction "1_1") (pintype "passive"))
      (node (ref "IC1") (pin "18") (pinfunction "AVCC_18") (pintype "power_in"))
      (node (ref "IC1") (pin "4") (pinfunction "VCC_4") (pintype "power_in"))
      (node (ref "IC1") (pin "6") (pinfunction "VCC_6") (pintype "power_in"))
      (node (ref "IC4") (pin "2") (pinfunction "OUT_2") (pintype "passive"))
      (node (ref "IC5") (pin "18") (pinfunction "VDD_18") (pintype "power_in"))
      (node (ref "IC5") (pin "6") (pinfunction "~{RST}_6") (pintype "input"))
      (node (ref "IC6") (pin "4") (pinfunction "VCC_4") (pintype "power_in"))
      (node (ref "L1") (pin "2") (pinfunction "2_2") (pintype "passive"))
      (node (ref "MICROSD") (pin "4") (pinfunction "VCC_4") (pintype "bidirectional"))
      (node (ref "RH") (pin "1") (pinfunction "1_1") (pintype "passive"))
      (node (ref "RN3") (pin "7") (pinfunction "2_7") (pintype "passive"))
      (node (ref "RN3") (pin "8") (pinfunction "2_8") (pintype "passive"))
      (node (ref "RRST") (pin "2") (pinfunction "2_2") (pintype "passive"))
      (node (ref "RSD") (pin "2") (pinfunction "2_2") (pintype "passive"))
      (node (ref "RTC") (pin "3") (pinfunction "VBAT_3") (pintype "power_in"))
      (node (ref "RTC") (pin "8") (pinfunction "VCC_8") (pintype "power_in"))
      (node (ref "RTCP1") (pin "1") (pinfunction "1_1") (pintype "passive"))
      (node (ref "RTCP2") (pin "1") (pinfunction "1_1") (pintype "passive"))
      (node (ref "RU") (pin "2") (pinfunction "2_2") (pintype "passive"))
      (node (ref "SV1") (pin "2") (pinfunction "2_2") (pintype "passive"))
      (node (ref "SV2") (pin "10") (pinfunction "10_10") (pintype "passive"))
      (node (ref "T1") (pin "1") (pinfunction "D_1") (pintype "passive"))
      (node (ref "T2") (pin "1") (pinfunction "D_1") (pintype "passive"))
      (node (ref "T3") (pin "1") (pinfunction "D_1") (pintype "passive"))
      (node (ref "U$1") (pin "P$3") (pinfunction "VDDA_P$3") (pintype "bidirectional"))
      (node (ref "U$1") (pin "P$4") (pinfunction "VDDD_P$4") (pintype "bidirectional"))
      (node (ref "U$1") (pin "P$8") (pinfunction "XCLR_P$8") (pintype "bidirectional"))
    )
    (net (code "69") (name "unconnected-(DHT22-Pad3)") (class "Default")
      (node (ref "DHT22") (pin "3") (pinfunction "3_3") (pintype "passive"))
    )
    (net (code "70") (name "unconnected-(IC1-ADC6-Pad19)") (class "Default")
      (node (ref "IC1") (pin "19") (pinfunction "ADC6_19") (pintype "bidirectional"))
    )
    (net (code "71") (name "unconnected-(IC1-ADC7-Pad22)") (class "Default")
      (node (ref "IC1") (pin "22") (pinfunction "ADC7_22") (pintype "bidirectional"))
    )
    (net (code "72") (name "unconnected-(IC5-~{INT}-Pad8)") (class "Default")
      (node (ref "IC5") (pin "8") (pinfunction "~{INT}_8") (pintype "output"))
    )
    (net (code "73") (name "unconnected-(IC7-CLKOUT-Pad3)") (class "Default")
      (node (ref "IC7") (pin "3") (pinfunction "CLKOUT_3") (pintype "bidirectional"))
    )
    (net (code "74") (name "unconnected-(IC7-NC-Pad5)") (class "Default")
      (node (ref "IC7") (pin "5") (pinfunction "NC_5") (pintype "bidirectional"))
    )
    (net (code "75") (name "unconnected-(IC7-{slash}INT-Pad4)") (class "Default")
      (node (ref "IC7") (pin "4") (pinfunction "/INT_4") (pintype "bidirectional"))
    )
    (net (code "76") (name "unconnected-(MICROSD-NC-Pad1)") (class "Default")
      (node (ref "MICROSD") (pin "1") (pinfunction "NC_1") (pintype "bidirectional"))
    )
    (net (code "77") (name "unconnected-(MICROSD-RSV-Pad8)") (class "Default")
      (node (ref "MICROSD") (pin "8") (pinfunction "RSV_8") (pintype "bidirectional"))
    )
    (net (code "78") (name "unconnected-(RJ45-PadNC)") (class "Default")
      (node (ref "RJ45") (pin "NC") (pinfunction "NC_NC") (pintype "bidirectional"))
    )
    (net (code "79") (name "unconnected-(RJ45-PadP5)") (class "Default")
      (node (ref "RJ45") (pin "P5") (pinfunction "P5_P5") (pintype "bidirectional"))
    )
    (net (code "80") (name "unconnected-(RTC-SQW{slash}OUT-Pad7)") (class "Default")
      (node (ref "RTC") (pin "7") (pinfunction "SQW/OUT_7") (pintype "bidirectional"))
    )
    (net (code "81") (name "unconnected-(U$1-EOC-PadP$2)") (class "Default")
      (node (ref "U$1") (pin "P$2") (pinfunction "EOC_P$2") (pintype "bidirectional"))
    )
  )
)
